# design.net
KiCad netlist of a schematic drawn in Altium Designer
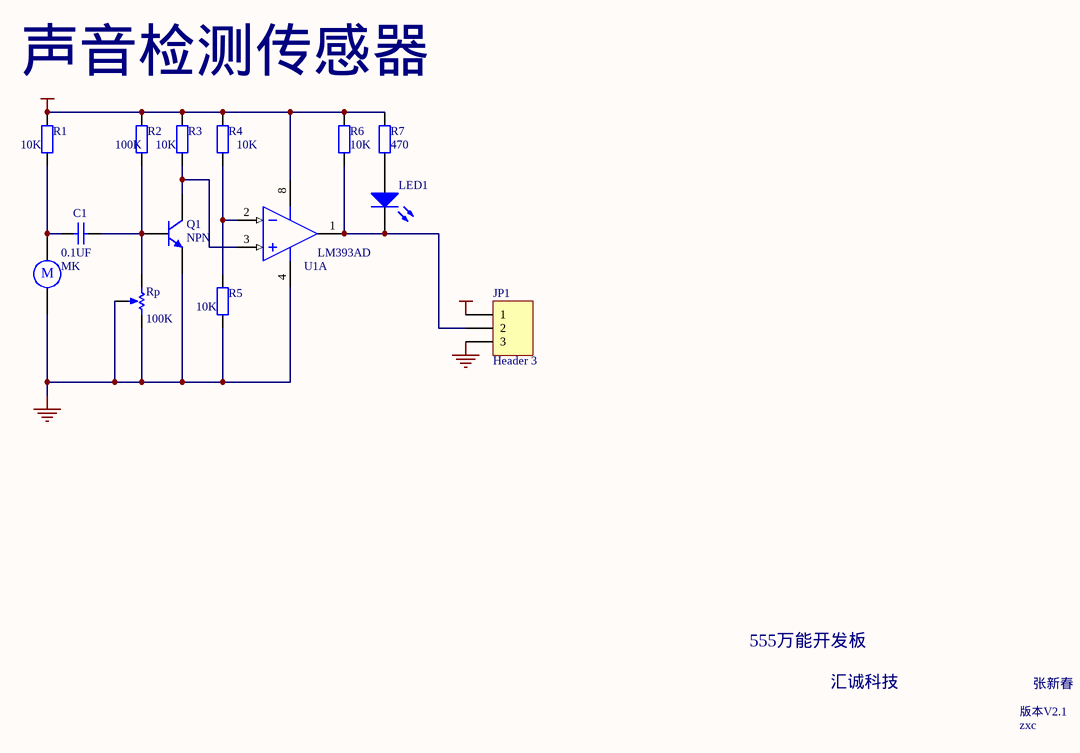
[diagram p0: 声音传感器.SchDoc]

(export (version "E")
  (design (tool "Eeschema 10.0.6"))
  (components
    (comp (ref "C1")
      (value "0.1UF")
      (footprint "C1608-0603")
      (description "Capacitor (Semiconductor SIM Model)")
      (fields (field (name "PUBLISHER") "Altium Limited"))
      (libsource (lib "Miscellaneous Devices") (part "Cap Semi"))
    )
    (comp (ref "JP1")
      (value "Header 3")
      (footprint "HDR1X3")
      (description "Header, 3-Pin")
      (fields (field (name "PUBLISHER") "Altium Limited"))
      (libsource (lib "Miscellaneous Connectors") (part "Header 3"))
    )
    (comp (ref "LED1")
      (value "~")
      (footprint "HDR1X2")
      (description "Typical BLUE SiC LED")
      (fields (field (name "PUBLISHER") "Altium Limited"))
      (libsource (lib "Miscellaneous Devices") (part "LED3"))
    )
    (comp (ref "MK")
      (value "~")
      (footprint "MK")
      (description "Motor, General Kind")
      (fields (field (name "PUBLISHER") "Altium Limited"))
      (libsource (lib "Miscellaneous Devices") (part "Motor"))
    )
    (comp (ref "Q1")
      (value "NPN")
      (footprint "SO-G3")
      (description "NPN Bipolar Transistor")
      (fields (field (name "PUBLISHER") "Altium Limited"))
      (libsource (lib "Miscellaneous Devices") (part "NPN"))
    )
    (comp (ref "R1")
      (value "10K")
      (footprint "C1608-0603")
      (description "Resistor")
      (fields (field (name "PUBLISHER") "Altium Limited"))
      (libsource (lib "") (part "Res2_1"))
    )
    (comp (ref "R2")
      (value "100K")
      (footprint "C1608-0603")
      (description "Resistor")
      (fields (field (name "PUBLISHER") "Altium Limited"))
      (libsource (lib "") (part "Res2_1"))
    )
    (comp (ref "R3")
      (value "10K")
      (footprint "C1608-0603")
      (description "Resistor")
      (fields (field (name "PUBLISHER") "Altium Limited"))
      (libsource (lib "") (part "Res2_1"))
    )
    (comp (ref "R4")
      (value "10K")
      (footprint "C1608-0603")
      (description "Resistor")
      (fields (field (name "PUBLISHER") "Altium Limited"))
      (libsource (lib "") (part "Res2_1"))
    )
    (comp (ref "R5")
      (value "10K")
      (footprint "C1608-0603")
      (description "Resistor")
      (fields (field (name "PUBLISHER") "Altium Limited"))
      (libsource (lib "") (part "Res2_1"))
    )
    (comp (ref "R6")
      (value "10K")
      (footprint "C1608-0603")
      (description "Resistor")
      (fields (field (name "PUBLISHER") "Altium Limited"))
      (libsource (lib "Miscellaneous Devices") (part "Res2"))
    )
    (comp (ref "R7")
      (value "470")
      (footprint "C1608-0603")
      (description "Resistor")
      (fields (field (name "PUBLISHER") "Altium Limited"))
      (libsource (lib "Miscellaneous Devices") (part "Res2"))
    )
    (comp (ref "Rp")
      (value "100K")
      (footprint "SIP3-D")
      (description "Potentiometer")
      (fields (field (name "PUBLISHER") "Altium Limited"))
      (libsource (lib "Miscellaneous Devices") (part "RPot"))
    )
    (comp (ref "U1")
      (value "LM393AD")
      (footprint "CDFP-8")
      (description "Low-Power Dual Voltage Comparator")
      (fields (field (name "PUBLISHER") "Altium Limited"))
      (libsource (lib "ST Analog Comparator") (part "LM393AD"))
    )
  )
  (nets
    (net (code "1") (name "GND") (class "Default")
      (node (ref "JP1") (pin "3") (pinfunction "3_3") (pintype "passive"))
      (node (ref "MK") (pin "2") (pinfunction "2_2") (pintype "passive"))
      (node (ref "Q1") (pin "2") (pinfunction "E_2") (pintype "passive"))
      (node (ref "R5") (pin "1") (pinfunction "1_1") (pintype "passive"))
      (node (ref "Rp") (pin "2") (pinfunction "BOT_2") (pintype "passive"))
      (node (ref "Rp") (pin "3") (pinfunction "TAP_3") (pintype "passive"))
      (node (ref "U1") (pin "4") (pinfunction "V-_4") (pintype "power_in"))
    )
    (net (code "2") (name "Net-(C1-Pad1)") (class "Default")
      (node (ref "C1") (pin "1") (pinfunction "1_1") (pintype "passive"))
      (node (ref "MK") (pin "1") (pinfunction "1_1") (pintype "passive"))
      (node (ref "R1") (pin "1") (pinfunction "1_1") (pintype "passive"))
    )
    (net (code "3") (name "Net-(LED1-A)") (class "Default")
      (node (ref "LED1") (pin "1") (pinfunction "A_1") (pintype "passive"))
      (node (ref "R7") (pin "2") (pinfunction "2_2") (pintype "passive"))
    )
    (net (code "4") (name "Net-(LED1-K)") (class "Default")
      (node (ref "JP1") (pin "2") (pinfunction "2_2") (pintype "passive"))
      (node (ref "LED1") (pin "2") (pinfunction "K_2") (pintype "passive"))
      (node (ref "R6") (pin "2") (pinfunction "2_2") (pintype "passive"))
      (node (ref "U1") (pin "1") (pinfunction "OUT_1") (pintype "open_collector"))
    )
    (net (code "5") (name "Net-(Q1-B)") (class "Default")
      (node (ref "C1") (pin "2") (pinfunction "2_2") (pintype "passive"))
      (node (ref "Q1") (pin "1") (pinfunction "B_1") (pintype "passive"))
      (node (ref "R2") (pin "1") (pinfunction "1_1") (pintype "passive"))
      (node (ref "Rp") (pin "1") (pinfunction "TOP_1") (pintype "passive"))
    )
    (net (code "6") (name "Net-(Q1-C)") (class "Default")
      (node (ref "Q1") (pin "3") (pinfunction "C_3") (pintype "passive"))
      (node (ref "R3") (pin "1") (pinfunction "1_1") (pintype "passive"))
      (node (ref "U1") (pin "3") (pinfunction "IN+_3") (pintype "input"))
    )
    (net (code "7") (name "Net-(U1A-IN-)") (class "Default")
      (node (ref "R4") (pin "1") (pinfunction "1_1") (pintype "passive"))
      (node (ref "R5") (pin "2") (pinfunction "2_2") (pintype "passive"))
      (node (ref "U1") (pin "2") (pinfunction "IN-_2") (pintype "input"))
    )
    (net (code "8") (name "VCC") (class "Default")
      (node (ref "JP1") (pin "1") (pinfunction "1_1") (pintype "passive"))
      (node (ref "R1") (pin "2") (pinfunction "2_2") (pintype "passive"))
      (node (ref "R2") (pin "2") (pinfunction "2_2") (pintype "passive"))
      (node (ref "R3") (pin "2") (pinfunction "2_2") (pintype "passive"))
      (node (ref "R4") (pin "2") (pinfunction "2_2") (pintype "passive"))
      (node (ref "R6") (pin "1") (pinfunction "1_1") (pintype "passive"))
      (node (ref "R7") (pin "1") (pinfunction "1_1") (pintype "passive"))
      (node (ref "U1") (pin "8") (pinfunction "V+_8") (pintype "power_in"))
    )
  )
)
